# FIT_FPGA_I-J-K.net
KiCad netlist of a schematic drawn in Altium Designer
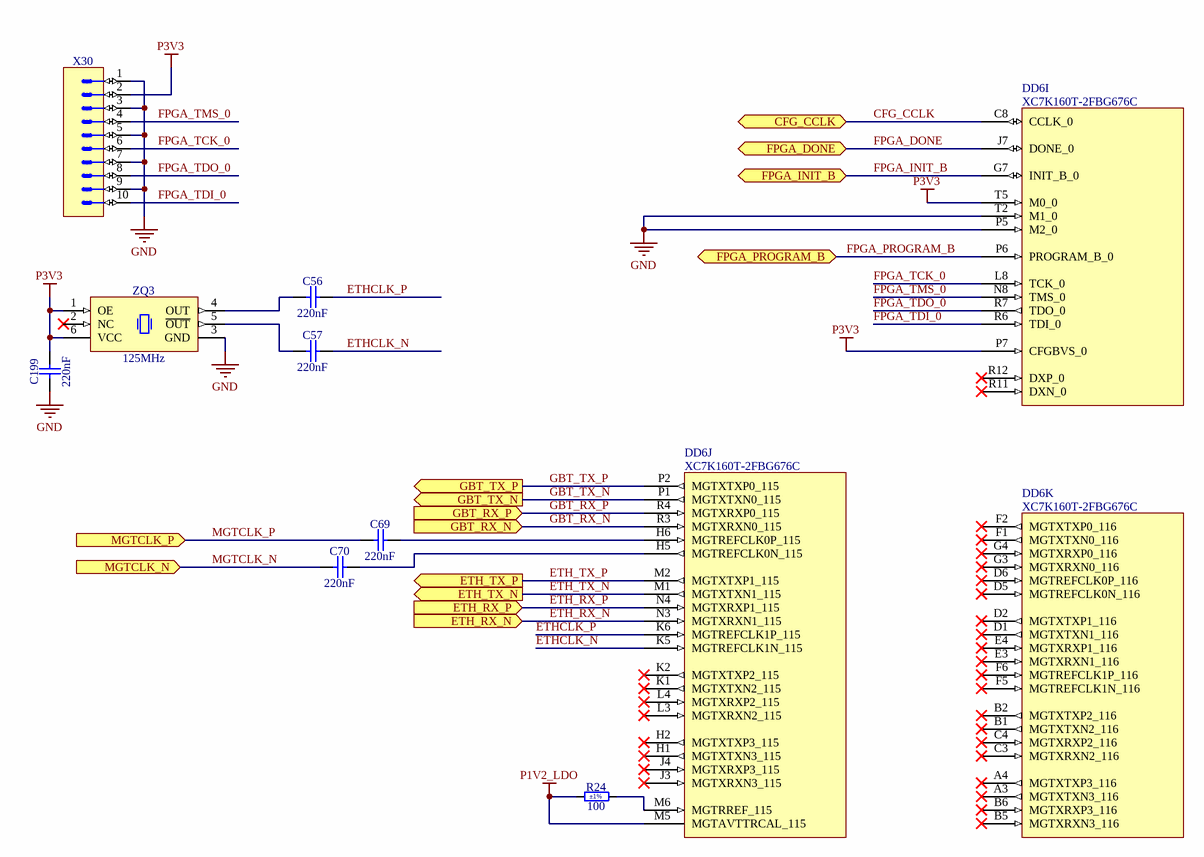
[diagram p0: FIT_FPGA_I-J-K.SchDoc]

(export (version "E")
  (design (tool "Eeschema 10.0.6"))
  (components
    (comp (ref "C56")
      (value "220nF")
      (footprint "CAPC1608X87N")
      (description "Non-polarised capacitor")
      (fields
        (field (name "PART NUMBER") "CC0603_220NF_25V_10%_X7R")
        (field (name "VOLTAGE") "25V")
        (field (name "AUTHOR") "CERN DEM JLC")
      )
      (libsource (lib "Capacitors") (part "Capacitor - non polarized"))
    )
    (comp (ref "C57")
      (value "220nF")
      (footprint "CAPC1608X87N")
      (description "Non-polarised capacitor")
      (fields
        (field (name "PART NUMBER") "CC0603_220NF_25V_10%_X7R")
        (field (name "VOLTAGE") "25V")
        (field (name "AUTHOR") "CERN DEM JLC")
      )
      (libsource (lib "Capacitors") (part "Capacitor - non polarized"))
    )
    (comp (ref "C69")
      (value "220nF")
      (footprint "CAPC1608X87N")
      (description "Non-polarised capacitor")
      (fields
        (field (name "PART NUMBER") "CC0603_220NF_25V_10%_X7R")
        (field (name "VOLTAGE") "25V")
        (field (name "AUTHOR") "CERN DEM JLC")
      )
      (libsource (lib "Capacitors") (part "Capacitor - non polarized"))
    )
    (comp (ref "C70")
      (value "220nF")
      (footprint "CAPC1608X87N")
      (description "Non-polarised capacitor")
      (fields
        (field (name "PART NUMBER") "CC0603_220NF_25V_10%_X7R")
        (field (name "VOLTAGE") "25V")
        (field (name "AUTHOR") "CERN DEM JLC")
      )
      (libsource (lib "Capacitors") (part "Capacitor - non polarized"))
    )
    (comp (ref "C199")
      (value "220nF")
      (footprint "CAPC2012X135N")
      (description "Non-polarised capacitor")
      (fields
        (field (name "PART NUMBER") "CC0805_220NF_50V_10%_X7R")
        (field (name "VOLTAGE") "50V")
        (field (name "AUTHOR") "CERN DEM JLC")
      )
      (libsource (lib "Capacitors") (part "Capacitor - non polarized"))
    )
    (comp (ref "DD6")
      (value "XC7K160T-2FBG676C")
      (footprint "BGA676C100P26X26_2700X2700X254")
      (description "KINTEX-7, FPGA, 676-Ball BGA, Pb-Free")
      (fields (field (name "MANUFACTURER") "XILINX") (field (name "AUTHOR") "CERN DEM BC"))
      (libsource (lib "ICs And Semiconductors") (part "XC7K160T-xFBG676"))
    )
    (comp (ref "R24")
      (value "100")
      (footprint "RESC1608X55N")
      (description "Resistor - 1%")
      (fields
        (field (name "TOLERANCE") "±1%")
        (field (name "PART NUMBER") "R0603_100R_1%_0.1W_100PPM")
        (field (name "POWER") "0.1W")
        (field (name "AUTHOR") "CERN DEM JLC")
      )
      (libsource (lib "Resistors") (part "Resistor - 1%"))
    )
    (comp (ref "X30")
      (value "~")
      (footprint "CONNFLY_DS1014-10SF1B-B")
      (description "Connector 10 Male")
      (fields
        (field (name "PART NUMBER") "CONNFLY_DS1014-10SF1B-B")
        (field (name "MANUFACTURER") "CONNFLY")
        (field (name "AUTHOR") "CERN DEM HF")
      )
      (libsource (lib "Connectors") (part "Connector 10 Male"))
    )
    (comp (ref "ZQ3")
      (value "125MHz")
      (footprint "OSC_EPSON_SG5032VAN")
      (description "Low-Jitter Saw Oscillator (EG-2102 Serie)")
      (fields
        (field (name "PART NUMBER") "OSC_125MHZ_EPSON_X1G0042610020")
        (field (name "MANUFACTURER") "EPSON")
        (field (name "AUTHOR") "CERN DEM HF")
      )
      (libsource (lib "ICs And Semiconductors") (part "Oscillator EPSON SG5032VAN"))
    )
  )
  (nets
    (net (code "1") (name "/CFG_CCLK") (class "Default")
      (node (ref "DD6") (pin "C8") (pinfunction "CCLK_0_C8") (pintype "bidirectional"))
    )
    (net (code "2") (name "/ETHCLK_N") (class "Default")
      (node (ref "C57") (pin "2") (pinfunction "2_2") (pintype "passive"))
      (node (ref "DD6") (pin "K5") (pinfunction "MGTREFCLK1N_115_K5") (pintype "input"))
    )
    (net (code "3") (name "/ETHCLK_P") (class "Default")
      (node (ref "C56") (pin "2") (pinfunction "2_2") (pintype "passive"))
      (node (ref "DD6") (pin "K6") (pinfunction "MGTREFCLK1P_115_K6") (pintype "input"))
    )
    (net (code "4") (name "/ETH_RX_N") (class "Default")
      (node (ref "DD6") (pin "N3") (pinfunction "MGTXRXN1_115_N3") (pintype "input"))
    )
    (net (code "5") (name "/ETH_RX_P") (class "Default")
      (node (ref "DD6") (pin "N4") (pinfunction "MGTXRXP1_115_N4") (pintype "input"))
    )
    (net (code "6") (name "/ETH_TX_N") (class "Default")
      (node (ref "DD6") (pin "M1") (pinfunction "MGTXTXN1_115_M1") (pintype "output"))
    )
    (net (code "7") (name "/ETH_TX_P") (class "Default")
      (node (ref "DD6") (pin "M2") (pinfunction "MGTXTXP1_115_M2") (pintype "output"))
    )
    (net (code "8") (name "/FPGA_DONE") (class "Default")
      (node (ref "DD6") (pin "J7") (pinfunction "DONE_0_J7") (pintype "bidirectional"))
    )
    (net (code "9") (name "/FPGA_INIT_B") (class "Default")
      (node (ref "DD6") (pin "G7") (pinfunction "INIT_B_0_G7") (pintype "bidirectional"))
    )
    (net (code "10") (name "/FPGA_PROGRAM_B") (class "Default")
      (node (ref "DD6") (pin "P6") (pinfunction "PROGRAM_B_0_P6") (pintype "input"))
    )
    (net (code "11") (name "/FPGA_TCK_0") (class "Default")
      (node (ref "DD6") (pin "L8") (pinfunction "TCK_0_L8") (pintype "input"))
      (node (ref "X30") (pin "6") (pinfunction "6_6") (pintype "bidirectional"))
    )
    (net (code "12") (name "/FPGA_TDI_0") (class "Default")
      (node (ref "DD6") (pin "R6") (pinfunction "TDI_0_R6") (pintype "input"))
      (node (ref "X30") (pin "10") (pinfunction "10_10") (pintype "bidirectional"))
    )
    (net (code "13") (name "/FPGA_TDO_0") (class "Default")
      (node (ref "DD6") (pin "R7") (pinfunction "TDO_0_R7") (pintype "output"))
      (node (ref "X30") (pin "8") (pinfunction "8_8") (pintype "bidirectional"))
    )
    (net (code "14") (name "/FPGA_TMS_0") (class "Default")
      (node (ref "DD6") (pin "N8") (pinfunction "TMS_0_N8") (pintype "input"))
      (node (ref "X30") (pin "4") (pinfunction "4_4") (pintype "bidirectional"))
    )
    (net (code "15") (name "/GBT_RX_N") (class "Default")
      (node (ref "DD6") (pin "R3") (pinfunction "MGTXRXN0_115_R3") (pintype "input"))
    )
    (net (code "16") (name "/GBT_RX_P") (class "Default")
      (node (ref "DD6") (pin "R4") (pinfunction "MGTXRXP0_115_R4") (pintype "input"))
    )
    (net (code "17") (name "/GBT_TX_N") (class "Default")
      (node (ref "DD6") (pin "P1") (pinfunction "MGTXTXN0_115_P1") (pintype "output"))
    )
    (net (code "18") (name "/GBT_TX_P") (class "Default")
      (node (ref "DD6") (pin "P2") (pinfunction "MGTXTXP0_115_P2") (pintype "output"))
    )
    (net (code "19") (name "/MGTCLK_N") (class "Default")
      (node (ref "C70") (pin "1") (pinfunction "1_1") (pintype "passive"))
    )
    (net (code "20") (name "/MGTCLK_P") (class "Default")
      (node (ref "C69") (pin "1") (pinfunction "1_1") (pintype "passive"))
    )
    (net (code "21") (name "GND") (class "Default")
      (node (ref "C199") (pin "1") (pinfunction "1_1") (pintype "passive"))
      (node (ref "DD6") (pin "P5") (pinfunction "M2_0_P5") (pintype "input"))
      (node (ref "DD6") (pin "T2") (pinfunction "M1_0_T2") (pintype "input"))
      (node (ref "X30") (pin "1") (pinfunction "1_1") (pintype "bidirectional"))
      (node (ref "X30") (pin "3") (pinfunction "3_3") (pintype "bidirectional"))
      (node (ref "X30") (pin "5") (pinfunction "5_5") (pintype "bidirectional"))
      (node (ref "X30") (pin "7") (pinfunction "7_7") (pintype "bidirectional"))
      (node (ref "X30") (pin "9") (pinfunction "9_9") (pintype "bidirectional"))
      (node (ref "ZQ3") (pin "3") (pinfunction "GND_3") (pintype "power_in"))
    )
    (net (code "22") (name "Net-(DD6J-MGTREFCLK0N_115)") (class "Default")
      (node (ref "C70") (pin "2") (pinfunction "2_2") (pintype "passive"))
      (node (ref "DD6") (pin "H5") (pinfunction "MGTREFCLK0N_115_H5") (pintype "output"))
    )
    (net (code "23") (name "Net-(DD6J-MGTREFCLK0P_115)") (class "Default")
      (node (ref "C69") (pin "2") (pinfunction "2_2") (pintype "passive"))
      (node (ref "DD6") (pin "H6") (pinfunction "MGTREFCLK0P_115_H6") (pintype "input"))
    )
    (net (code "24") (name "Net-(DD6J-MGTRREF_115)") (class "Default")
      (node (ref "DD6") (pin "M6") (pinfunction "MGTRREF_115_M6") (pintype "input"))
      (node (ref "R24") (pin "2") (pinfunction "2_2") (pintype "passive"))
    )
    (net (code "25") (name "Net-(ZQ3-OUT)") (class "Default")
      (node (ref "C56") (pin "1") (pinfunction "1_1") (pintype "passive"))
      (node (ref "ZQ3") (pin "4") (pinfunction "OUT_4") (pintype "output"))
    )
    (net (code "26") (name "Net-(ZQ3-~{OUT})") (class "Default")
      (node (ref "C57") (pin "1") (pinfunction "1_1") (pintype "passive"))
      (node (ref "ZQ3") (pin "5") (pinfunction "~{OUT}_5") (pintype "output"))
    )
    (net (code "27") (name "P1V2_LDO") (class "Default")
      (node (ref "DD6") (pin "M5") (pinfunction "MGTAVTTRCAL_115_M5") (pintype "passive"))
      (node (ref "R24") (pin "1") (pinfunction "1_1") (pintype "passive"))
    )
    (net (code "28") (name "P3V3") (class "Default")
      (node (ref "C199") (pin "2") (pinfunction "2_2") (pintype "passive"))
      (node (ref "DD6") (pin "P7") (pinfunction "CFGBVS_0_P7") (pintype "input"))
      (node (ref "DD6") (pin "T5") (pinfunction "M0_0_T5") (pintype "input"))
      (node (ref "X30") (pin "2") (pinfunction "2_2") (pintype "bidirectional"))
      (node (ref "ZQ3") (pin "1") (pinfunction "OE_1") (pintype "input"))
      (node (ref "ZQ3") (pin "6") (pinfunction "VCC_6") (pintype "power_in"))
    )
    (net (code "29") (name "unconnected-(DD6I-DXN_0-PadR11)") (class "Default")
      (node (ref "DD6") (pin "R11") (pinfunction "DXN_0_R11") (pintype "input+no_connect"))
    )
    (net (code "30") (name "unconnected-(DD6I-DXP_0-PadR12)") (class "Default")
      (node (ref "DD6") (pin "R12") (pinfunction "DXP_0_R12") (pintype "input+no_connect"))
    )
    (net (code "31") (name "unconnected-(DD6J-MGTXRXN2_115-PadL3)") (class "Default")
      (node (ref "DD6") (pin "L3") (pinfunction "MGTXRXN2_115_L3") (pintype "input+no_connect"))
    )
    (net (code "32") (name "unconnected-(DD6J-MGTXRXN3_115-PadJ3)") (class "Default")
      (node (ref "DD6") (pin "J3") (pinfunction "MGTXRXN3_115_J3") (pintype "input+no_connect"))
    )
    (net (code "33") (name "unconnected-(DD6J-MGTXRXP2_115-PadL4)") (class "Default")
      (node (ref "DD6") (pin "L4") (pinfunction "MGTXRXP2_115_L4") (pintype "input+no_connect"))
    )
    (net (code "34") (name "unconnected-(DD6J-MGTXRXP3_115-PadJ4)") (class "Default")
      (node (ref "DD6") (pin "J4") (pinfunction "MGTXRXP3_115_J4") (pintype "input+no_connect"))
    )
    (net (code "35") (name "unconnected-(DD6J-MGTXTXN2_115-PadK1)") (class "Default")
      (node (ref "DD6") (pin "K1") (pinfunction "MGTXTXN2_115_K1") (pintype "output+no_connect"))
    )
    (net (code "36") (name "unconnected-(DD6J-MGTXTXN3_115-PadH1)") (class "Default")
      (node (ref "DD6") (pin "H1") (pinfunction "MGTXTXN3_115_H1") (pintype "output+no_connect"))
    )
    (net (code "37") (name "unconnected-(DD6J-MGTXTXP2_115-PadK2)") (class "Default")
      (node (ref "DD6") (pin "K2") (pinfunction "MGTXTXP2_115_K2") (pintype "output+no_connect"))
    )
    (net (code "38") (name "unconnected-(DD6J-MGTXTXP3_115-PadH2)") (class "Default")
      (node (ref "DD6") (pin "H2") (pinfunction "MGTXTXP3_115_H2") (pintype "output+no_connect"))
    )
    (net (code "39") (name "unconnected-(DD6K-MGTREFCLK0N_116-PadD5)") (class "Default")
      (node (ref "DD6") (pin "D5") (pinfunction "MGTREFCLK0N_116_D5") (pintype "input+no_connect"))
    )
    (net (code "40") (name "unconnected-(DD6K-MGTREFCLK0P_116-PadD6)") (class "Default")
      (node (ref "DD6") (pin "D6") (pinfunction "MGTREFCLK0P_116_D6") (pintype "input+no_connect"))
    )
    (net (code "41") (name "unconnected-(DD6K-MGTREFCLK1N_116-PadF5)") (class "Default")
      (node (ref "DD6") (pin "F5") (pinfunction "MGTREFCLK1N_116_F5") (pintype "input+no_connect"))
    )
    (net (code "42") (name "unconnected-(DD6K-MGTREFCLK1P_116-PadF6)") (class "Default")
      (node (ref "DD6") (pin "F6") (pinfunction "MGTREFCLK1P_116_F6") (pintype "input+no_connect"))
    )
    (net (code "43") (name "unconnected-(DD6K-MGTXRXN0_116-PadG3)") (class "Default")
      (node (ref "DD6") (pin "G3") (pinfunction "MGTXRXN0_116_G3") (pintype "input+no_connect"))
    )
    (net (code "44") (name "unconnected-(DD6K-MGTXRXN1_116-PadE3)") (class "Default")
      (node (ref "DD6") (pin "E3") (pinfunction "MGTXRXN1_116_E3") (pintype "input+no_connect"))
    )
    (net (code "45") (name "unconnected-(DD6K-MGTXRXN2_116-PadC3)") (class "Default")
      (node (ref "DD6") (pin "C3") (pinfunction "MGTXRXN2_116_C3") (pintype "input+no_connect"))
    )
    (net (code "46") (name "unconnected-(DD6K-MGTXRXN3_116-PadB5)") (class "Default")
      (node (ref "DD6") (pin "B5") (pinfunction "MGTXRXN3_116_B5") (pintype "input+no_connect"))
    )
    (net (code "47") (name "unconnected-(DD6K-MGTXRXP0_116-PadG4)") (class "Default")
      (node (ref "DD6") (pin "G4") (pinfunction "MGTXRXP0_116_G4") (pintype "input+no_connect"))
    )
    (net (code "48") (name "unconnected-(DD6K-MGTXRXP1_116-PadE4)") (class "Default")
      (node (ref "DD6") (pin "E4") (pinfunction "MGTXRXP1_116_E4") (pintype "input+no_connect"))
    )
    (net (code "49") (name "unconnected-(DD6K-MGTXRXP2_116-PadC4)") (class "Default")
      (node (ref "DD6") (pin "C4") (pinfunction "MGTXRXP2_116_C4") (pintype "input+no_connect"))
    )
    (net (code "50") (name "unconnected-(DD6K-MGTXRXP3_116-PadB6)") (class "Default")
      (node (ref "DD6") (pin "B6") (pinfunction "MGTXRXP3_116_B6") (pintype "input+no_connect"))
    )
    (net (code "51") (name "unconnected-(DD6K-MGTXTXN0_116-PadF1)") (class "Default")
      (node (ref "DD6") (pin "F1") (pinfunction "MGTXTXN0_116_F1") (pintype "output+no_connect"))
    )
    (net (code "52") (name "unconnected-(DD6K-MGTXTXN1_116-PadD1)") (class "Default")
      (node (ref "DD6") (pin "D1") (pinfunction "MGTXTXN1_116_D1") (pintype "output+no_connect"))
    )
    (net (code "53") (name "unconnected-(DD6K-MGTXTXN2_116-PadB1)") (class "Default")
      (node (ref "DD6") (pin "B1") (pinfunction "MGTXTXN2_116_B1") (pintype "output+no_connect"))
    )
    (net (code "54") (name "unconnected-(DD6K-MGTXTXN3_116-PadA3)") (class "Default")
      (node (ref "DD6") (pin "A3") (pinfunction "MGTXTXN3_116_A3") (pintype "output+no_connect"))
    )
    (net (code "55") (name "unconnected-(DD6K-MGTXTXP0_116-PadF2)") (class "Default")
      (node (ref "DD6") (pin "F2") (pinfunction "MGTXTXP0_116_F2") (pintype "output+no_connect"))
    )
    (net (code "56") (name "unconnected-(DD6K-MGTXTXP1_116-PadD2)") (class "Default")
      (node (ref "DD6") (pin "D2") (pinfunction "MGTXTXP1_116_D2") (pintype "output+no_connect"))
    )
    (net (code "57") (name "unconnected-(DD6K-MGTXTXP2_116-PadB2)") (class "Default")
      (node (ref "DD6") (pin "B2") (pinfunction "MGTXTXP2_116_B2") (pintype "output+no_connect"))
    )
    (net (code "58") (name "unconnected-(DD6K-MGTXTXP3_116-PadA4)") (class "Default")
      (node (ref "DD6") (pin "A4") (pinfunction "MGTXTXP3_116_A4") (pintype "output+no_connect"))
    )
    (net (code "59") (name "unconnected-(ZQ3-NC-Pad2)") (class "Default")
      (node (ref "ZQ3") (pin "2") (pinfunction "NC_2") (pintype "input+no_connect"))
    )
  )
)
